# SerialResetBoard.net
KiCad netlist of a schematic drawn in EAGLE
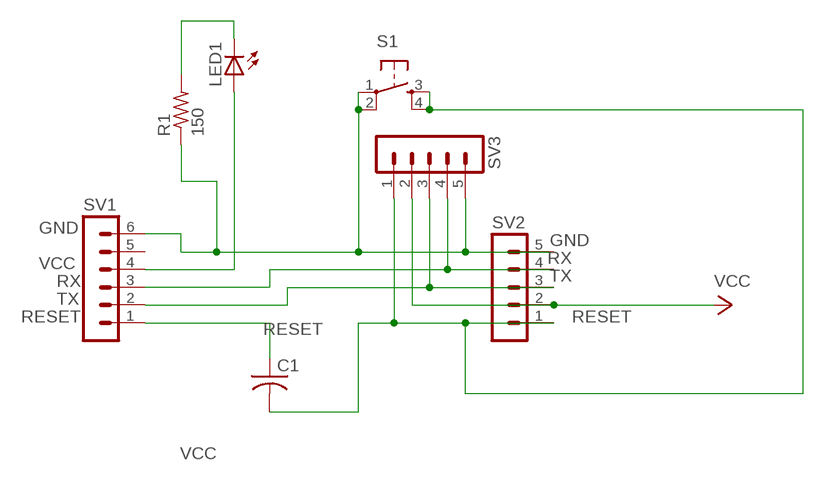
[diagram p0: schematic, sheet 1]

(export (version "E")
  (design (tool "Eeschema 10.0.6"))
  (components
    (comp (ref "C1")
      (value "C-US025-024X044")
      (footprint "eagle-import:C025-024X044")
      (libsource (lib "eagle-import") (part "C-US025-024X044"))
    )
    (comp (ref "LED1")
      (value "LED3MM")
      (footprint "eagle-import:LED3MM")
      (libsource (lib "eagle-import") (part "LED3MM"))
    )
    (comp (ref "R1")
      (value "150")
      (footprint "eagle-import:0207_7")
      (libsource (lib "eagle-import") (part "R-US_0207/7"))
    )
    (comp (ref "S1")
      (value "TAC_SWITCHPTH")
      (footprint "eagle-import:TACTILE-PTH")
      (libsource (lib "eagle-import") (part "TAC_SWITCHPTH"))
    )
    (comp (ref "SV1")
      (value "MA06-1")
      (footprint "eagle-import:MA06-1")
      (libsource (lib "eagle-import") (part "MA06-1"))
    )
    (comp (ref "SV2")
      (value "MA05-1")
      (footprint "eagle-import:MA05-1")
      (libsource (lib "eagle-import") (part "MA05-1"))
    )
    (comp (ref "SV3")
      (value "MA05-1")
      (footprint "eagle-import:MA05-1")
      (libsource (lib "eagle-import") (part "MA05-1"))
    )
  )
  (nets
    (net (code "1") (name "/GND") (class "Default")
      (node (ref "R1") (pin "1") (pinfunction "1_1") (pintype "passive"))
      (node (ref "S1") (pin "1") (pinfunction "1_1") (pintype "passive"))
      (node (ref "S1") (pin "2") (pinfunction "2_2") (pintype "passive"))
      (node (ref "SV1") (pin "6") (pinfunction "6_6") (pintype "passive"))
      (node (ref "SV2") (pin "5") (pinfunction "5_5") (pintype "passive"))
      (node (ref "SV3") (pin "5") (pinfunction "5_5") (pintype "passive"))
    )
    (net (code "2") (name "/RESET") (class "Default")
      (node (ref "C1") (pin "2") (pinfunction "2_2") (pintype "passive"))
      (node (ref "S1") (pin "3") (pinfunction "3_3") (pintype "passive"))
      (node (ref "S1") (pin "4") (pinfunction "4_4") (pintype "passive"))
      (node (ref "SV2") (pin "1") (pinfunction "1_1") (pintype "passive"))
      (node (ref "SV3") (pin "1") (pinfunction "1_1") (pintype "passive"))
    )
    (net (code "3") (name "/RX") (class "Default")
      (node (ref "SV1") (pin "3") (pinfunction "3_3") (pintype "passive"))
      (node (ref "SV2") (pin "4") (pinfunction "4_4") (pintype "passive"))
      (node (ref "SV3") (pin "4") (pinfunction "4_4") (pintype "passive"))
    )
    (net (code "4") (name "/TX") (class "Default")
      (node (ref "SV1") (pin "2") (pinfunction "2_2") (pintype "passive"))
      (node (ref "SV2") (pin "3") (pinfunction "3_3") (pintype "passive"))
      (node (ref "SV3") (pin "3") (pinfunction "3_3") (pintype "passive"))
    )
    (net (code "5") (name "Net-(C1-Pad1)") (class "Default")
      (node (ref "C1") (pin "1") (pinfunction "1_1") (pintype "passive"))
      (node (ref "SV1") (pin "1") (pinfunction "1_1") (pintype "passive"))
    )
    (net (code "6") (name "Net-(LED1-C)") (class "Default")
      (node (ref "LED1") (pin "K") (pinfunction "C_K") (pintype "passive"))
      (node (ref "R1") (pin "2") (pinfunction "2_2") (pintype "passive"))
    )
    (net (code "7") (name "VCC") (class "Default")
      (node (ref "LED1") (pin "A") (pinfunction "A_A") (pintype "passive"))
      (node (ref "SV1") (pin "4") (pinfunction "4_4") (pintype "passive"))
      (node (ref "SV2") (pin "2") (pinfunction "2_2") (pintype "passive"))
      (node (ref "SV3") (pin "2") (pinfunction "2_2") (pintype "passive"))
    )
    (net (code "8") (name "unconnected-(SV1-Pad5)") (class "Default")
      (node (ref "SV1") (pin "5") (pinfunction "5_5") (pintype "passive"))
    )
  )
)
